# Power.net
KiCad netlist of a schematic drawn in Altium Designer
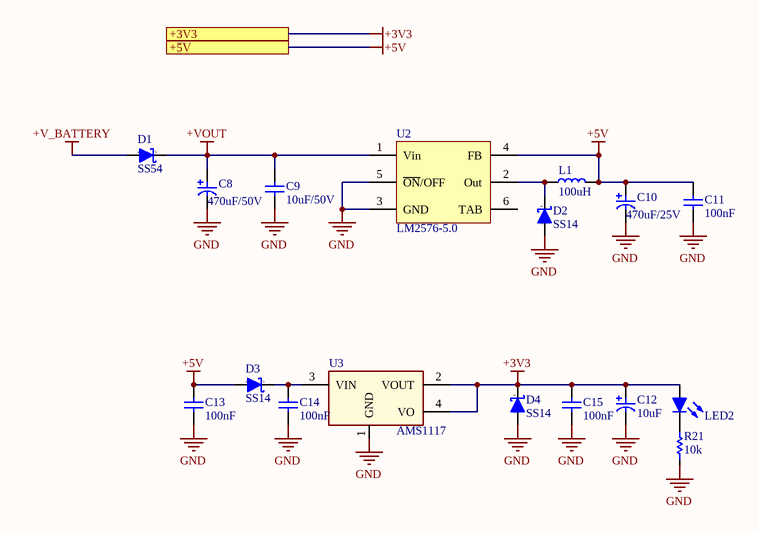
[diagram p0: Power.SchDoc]

(export (version "E")
  (design (tool "Eeschema 10.0.6"))
  (components
    (comp (ref "C8")
      (value "470uF/50V")
      (footprint "C SMD ALU (G)")
      (description "Capacitor pol")
      (libsource (lib "BKIT4U_LIB_NEW") (part "Capacitor"))
    )
    (comp (ref "C9")
      (value "10uF/50V")
      (footprint "C 0603 (1608)")
      (description "Capacitor non-pol")
      (libsource (lib "BKIT4U_LIB_NEW") (part "Capacitor NP"))
    )
    (comp (ref "C10")
      (value "470uF/25V")
      (footprint "C SMD ALU (G)")
      (description "Capacitor pol")
      (libsource (lib "BKIT4U_LIB_NEW") (part "Capacitor"))
    )
    (comp (ref "C11")
      (value "100nF")
      (footprint "C 0603 (1608)")
      (description "Capacitor non-pol")
      (libsource (lib "BKIT4U_LIB_NEW") (part "Capacitor NP"))
    )
    (comp (ref "C12")
      (value "10uF")
      (footprint "C SMD ALU (B)")
      (description "Capacitor pol")
      (libsource (lib "BKIT4U_LIB_NEW") (part "Capacitor"))
    )
    (comp (ref "C13")
      (value "100nF")
      (footprint "C 0603 (1608)")
      (description "Capacitor non-pol")
      (libsource (lib "BKIT4U_LIB_NEW") (part "Capacitor NP"))
    )
    (comp (ref "C14")
      (value "100nF")
      (footprint "C 0603 (1608)")
      (description "Capacitor non-pol")
      (libsource (lib "BKIT4U_LIB_NEW") (part "Capacitor NP"))
    )
    (comp (ref "C15")
      (value "100nF")
      (footprint "C 0603 (1608)")
      (description "Capacitor non-pol")
      (libsource (lib "BKIT4U_LIB_NEW") (part "Capacitor NP"))
    )
    (comp (ref "D1")
      (value "SS54")
      (footprint "DO-214AC (SMA)")
      (description "Schottky Diode")
      (fields (field (name "PUBLISHER") "Altium Limited"))
      (libsource (lib "BKIT4U_LIB_NEW") (part "Diode Schottky"))
    )
    (comp (ref "D2")
      (value "SS14")
      (footprint "DO-214AC (SMA)")
      (description "Schottky Diode")
      (fields (field (name "PUBLISHER") "Altium Limited"))
      (libsource (lib "BKIT4U_LIB_NEW") (part "Diode Schottky"))
    )
    (comp (ref "D3")
      (value "SS14")
      (footprint "DO-214AC (SMA)")
      (description "Schottky Diode")
      (fields (field (name "PUBLISHER") "Altium Limited"))
      (libsource (lib "BKIT4U_LIB_NEW") (part "Diode Schottky"))
    )
    (comp (ref "D4")
      (value "SS14")
      (footprint "DO-214AC (SMA)")
      (description "Schottky Diode")
      (fields (field (name "PUBLISHER") "Altium Limited"))
      (libsource (lib "BKIT4U_LIB_NEW") (part "Diode Schottky"))
    )
    (comp (ref "L1")
      (value "100uH")
      (footprint "Inductor SMD 0805 (2012)")
      (description "Inductor")
      (libsource (lib "BKIT4U_LIB_NEW") (part "Inductor"))
    )
    (comp (ref "LED2")
      (value "Led")
      (footprint "Led SMD 0603")
      (description "Typical LED")
      (libsource (lib "BKIT4U_LIB_NEW") (part "Led"))
    )
    (comp (ref "R21")
      (value "10k")
      (footprint "R 0603 (1608)")
      (description "Resistor")
      (fields (field (name "PUBLISHER") "Altium Limited"))
      (libsource (lib "BKIT4U_LIB_NEW") (part "Resistor"))
    )
    (comp (ref "U2")
      (value "LM2576-5.0")
      (footprint "TO-263-5")
      (description "SIMPLE SWITCHER® 3A Step-Down Voltage Regulator")
      (libsource (lib "BKIT4U_LIB_NEW") (part "LM2576/96"))
    )
    (comp (ref "U3")
      (value "AMS1117")
      (footprint "SOT-223")
      (description "1A LDO Voltage Regulator, ADJ or fixed 1.5/1.8/2.5/2.85/3.3/5V")
      (libsource (lib "BKIT4U_LIB_NEW") (part "AMS1117"))
    )
  )
  (nets
    (net (code "1") (name "+3V3") (class "Default")
      (node (ref "C12") (pin "1") (pinfunction "1_1") (pintype "passive"))
      (node (ref "C15") (pin "1") (pinfunction "1_1") (pintype "passive"))
      (node (ref "D4") (pin "1") (pinfunction "A_1") (pintype "passive"))
      (node (ref "LED2") (pin "2") (pinfunction "A_2") (pintype "passive"))
      (node (ref "U3") (pin "2") (pinfunction "VOUT_2") (pintype "passive"))
      (node (ref "U3") (pin "4") (pinfunction "VO_4") (pintype "passive"))
    )
    (net (code "2") (name "+5V") (class "Default")
      (node (ref "C10") (pin "1") (pinfunction "1_1") (pintype "passive"))
      (node (ref "C11") (pin "1") (pinfunction "1_1") (pintype "passive"))
      (node (ref "C13") (pin "1") (pinfunction "1_1") (pintype "passive"))
      (node (ref "D3") (pin "2") (pinfunction "K_2") (pintype "passive"))
      (node (ref "L1") (pin "2") (pinfunction "2_2") (pintype "passive"))
      (node (ref "U2") (pin "4") (pinfunction "FB_4") (pintype "passive"))
    )
    (net (code "3") (name "+VOUT") (class "Default")
      (node (ref "C8") (pin "1") (pinfunction "1_1") (pintype "passive"))
      (node (ref "C9") (pin "1") (pinfunction "1_1") (pintype "passive"))
      (node (ref "D1") (pin "1") (pinfunction "A_1") (pintype "passive"))
      (node (ref "U2") (pin "1") (pinfunction "Vin_1") (pintype "passive"))
    )
    (net (code "4") (name "+V_BATTERY") (class "Default")
      (node (ref "D1") (pin "2") (pinfunction "K_2") (pintype "passive"))
    )
    (net (code "5") (name "GND") (class "Default")
      (node (ref "C10") (pin "2") (pinfunction "2_2") (pintype "passive"))
      (node (ref "C11") (pin "2") (pinfunction "2_2") (pintype "passive"))
      (node (ref "C12") (pin "2") (pinfunction "2_2") (pintype "passive"))
      (node (ref "C13") (pin "2") (pinfunction "2_2") (pintype "passive"))
      (node (ref "C14") (pin "2") (pinfunction "2_2") (pintype "passive"))
      (node (ref "C15") (pin "2") (pinfunction "2_2") (pintype "passive"))
      (node (ref "C8") (pin "2") (pinfunction "2_2") (pintype "passive"))
      (node (ref "C9") (pin "2") (pinfunction "2_2") (pintype "passive"))
      (node (ref "D2") (pin "2") (pinfunction "K_2") (pintype "passive"))
      (node (ref "D4") (pin "2") (pinfunction "K_2") (pintype "passive"))
      (node (ref "R21") (pin "1") (pinfunction "1_1") (pintype "passive"))
      (node (ref "U2") (pin "3") (pinfunction "GND_3") (pintype "passive"))
      (node (ref "U2") (pin "5") (pinfunction "~{ON}/OFF_5") (pintype "passive"))
      (node (ref "U3") (pin "1") (pinfunction "GND_1") (pintype "passive"))
    )
    (net (code "6") (name "Net-(D2-A)") (class "Default")
      (node (ref "D2") (pin "1") (pinfunction "A_1") (pintype "passive"))
      (node (ref "L1") (pin "1") (pinfunction "1_1") (pintype "passive"))
      (node (ref "U2") (pin "2") (pinfunction "Out_2") (pintype "passive"))
    )
    (net (code "7") (name "Net-(D3-A)") (class "Default")
      (node (ref "C14") (pin "1") (pinfunction "1_1") (pintype "passive"))
      (node (ref "D3") (pin "1") (pinfunction "A_1") (pintype "passive"))
      (node (ref "U3") (pin "3") (pinfunction "VIN_3") (pintype "power_in"))
    )
    (net (code "8") (name "Net-(LED2-K)") (class "Default")
      (node (ref "LED2") (pin "1") (pinfunction "K_1") (pintype "passive"))
      (node (ref "R21") (pin "2") (pinfunction "2_2") (pintype "passive"))
    )
    (net (code "9") (name "unconnected-(U2-TAB-Pad6)") (class "Default")
      (node (ref "U2") (pin "6") (pinfunction "TAB_6") (pintype "passive"))
    )
  )
)
